# Teensy_CARD_V2.net
KiCad netlist of a schematic drawn in EAGLE
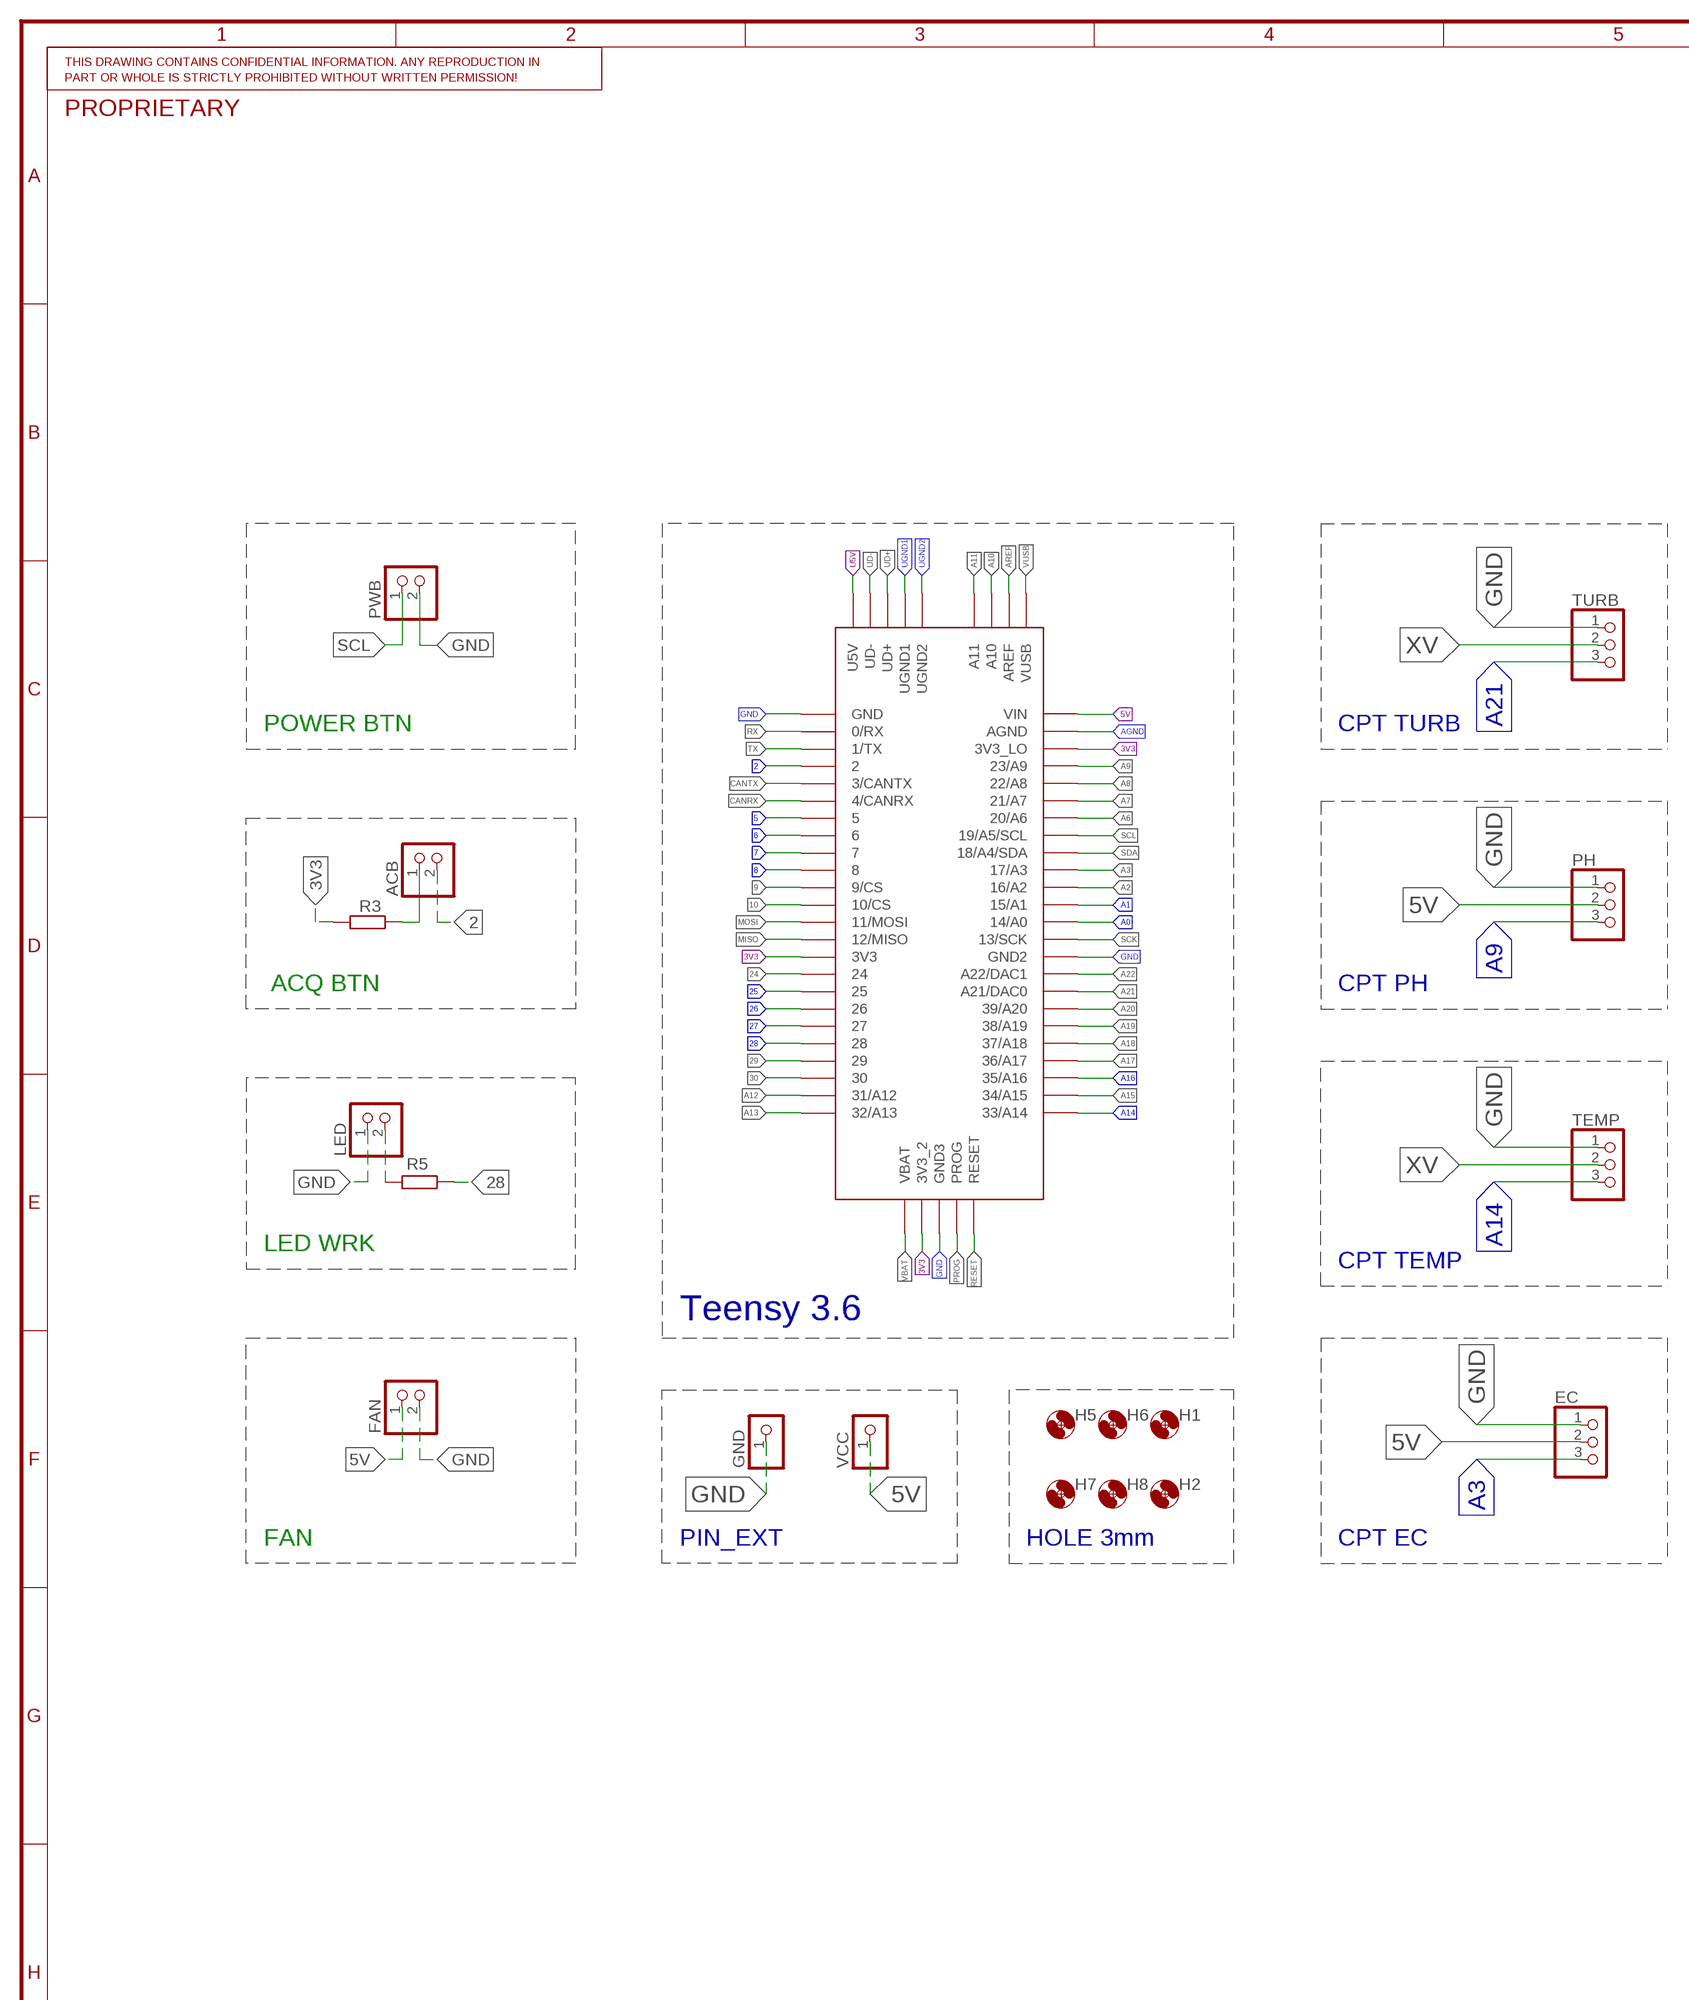
[diagram p0: schematic, sheet 1, part 1 of 2]
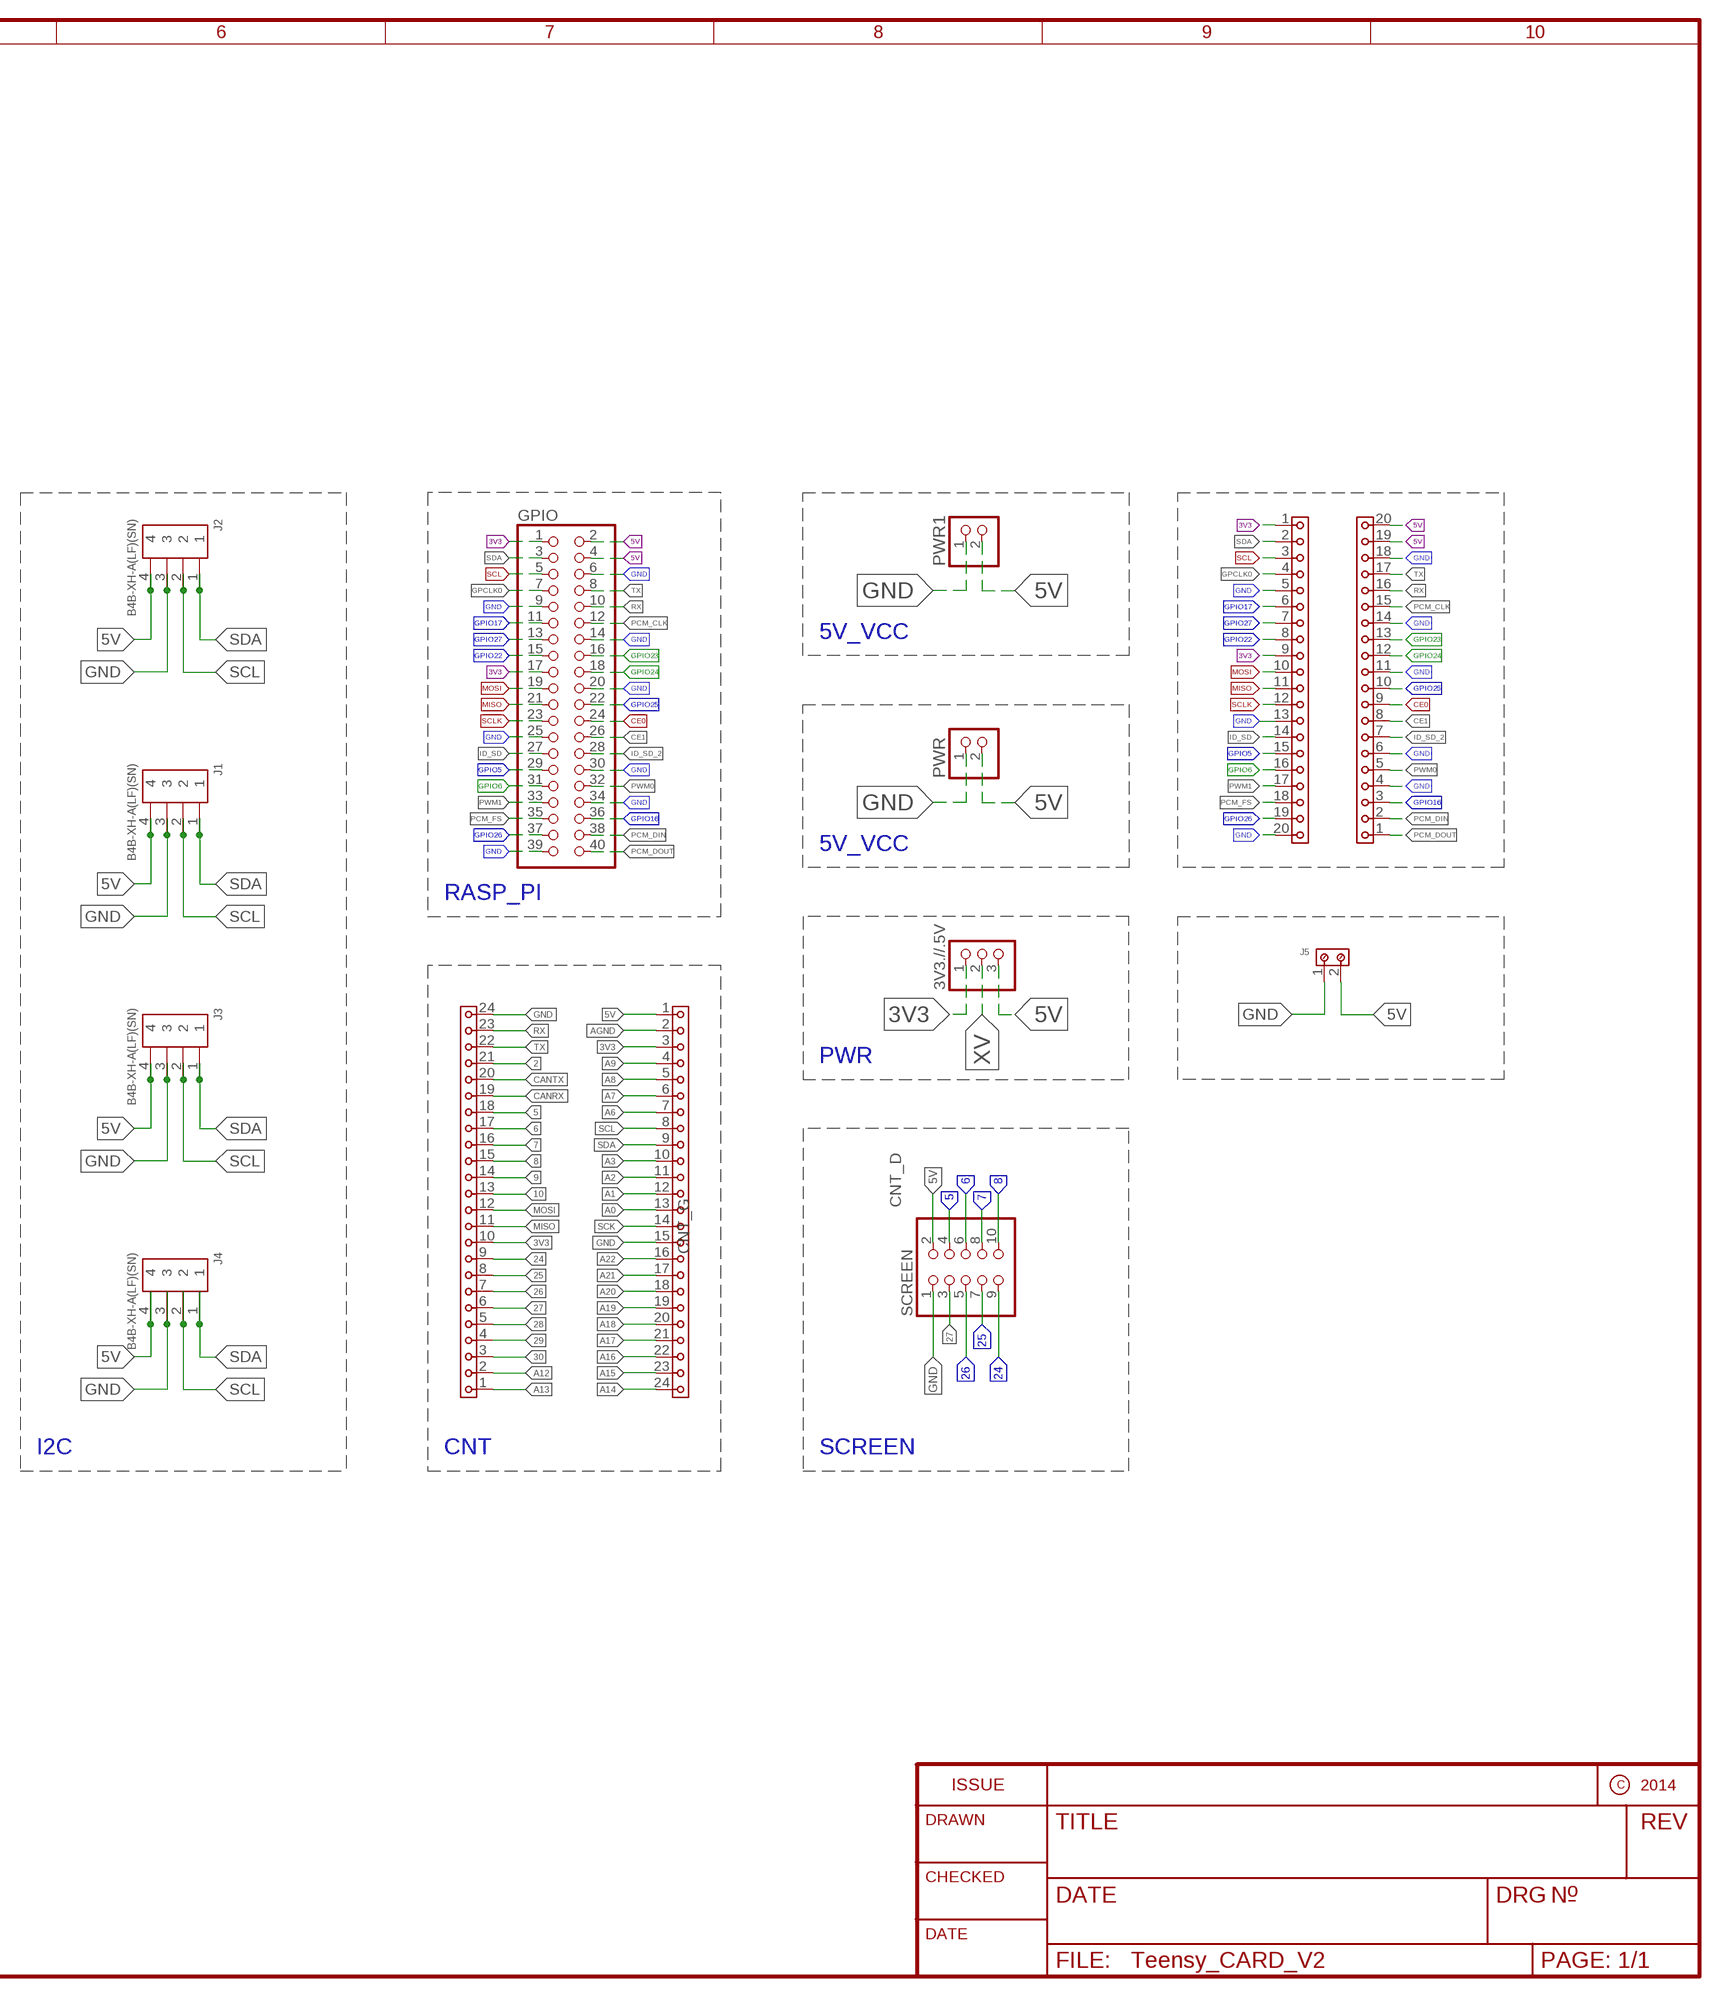
[diagram p1: schematic, sheet 1, part 2 of 2]

(export (version "E")
  (design (tool "Eeschema 10.0.6"))
  (components
    (comp (ref "3V3.//.5V")
      (value "PINHD-1X3")
      (footprint "eagle-import:1X03")
      (libsource (lib "eagle-import") (part "PINHD-1X3"))
    )
    (comp (ref "ACB")
      (value "PINHD-1X2")
      (footprint "eagle-import:1X02")
      (libsource (lib "eagle-import") (part "pinhead_325_PINHD-1X2"))
    )
    (comp (ref "CNT_D")
      (value "6130XX11821_61302411821")
      (footprint "eagle-import:61302411821")
      (libsource (lib "eagle-import") (part "6130XX11821_61302411821"))
    )
    (comp (ref "CNT_G")
      (value "6130XX11821_61302411821")
      (footprint "eagle-import:61302411821")
      (libsource (lib "eagle-import") (part "6130XX11821_61302411821"))
    )
    (comp (ref "EC")
      (value "PINHD-1X3")
      (footprint "eagle-import:1X03")
      (libsource (lib "eagle-import") (part "PINHD-1X3"))
    )
    (comp (ref "FAN")
      (value "PINHD-1X2")
      (footprint "eagle-import:1X02")
      (libsource (lib "eagle-import") (part "pinhead_325_PINHD-1X2"))
    )
    (comp (ref "GND")
      (value "PINHD-1X1")
      (footprint "eagle-import:1X01")
      (libsource (lib "eagle-import") (part "PINHD-1X1"))
    )
    (comp (ref "GPIO")
      (value "PINHD-2X20")
      (footprint "eagle-import:2X20")
      (libsource (lib "eagle-import") (part "PINHD-2X20"))
    )
    (comp (ref "H1")
      (value "MOUNT-HOLE3.0")
      (footprint "eagle-import:3,0")
      (libsource (lib "eagle-import") (part "MOUNT-HOLE3.0"))
    )
    (comp (ref "H2")
      (value "MOUNT-HOLE3.0")
      (footprint "eagle-import:3,0")
      (libsource (lib "eagle-import") (part "MOUNT-HOLE3.0"))
    )
    (comp (ref "H5")
      (value "MOUNT-HOLE3.0")
      (footprint "eagle-import:3,0")
      (libsource (lib "eagle-import") (part "MOUNT-HOLE3.0"))
    )
    (comp (ref "H6")
      (value "MOUNT-HOLE3.0")
      (footprint "eagle-import:3,0")
      (libsource (lib "eagle-import") (part "MOUNT-HOLE3.0"))
    )
    (comp (ref "H7")
      (value "MOUNT-HOLE3.0")
      (footprint "eagle-import:3,0")
      (libsource (lib "eagle-import") (part "MOUNT-HOLE3.0"))
    )
    (comp (ref "H8")
      (value "MOUNT-HOLE3.0")
      (footprint "eagle-import:3,0")
      (libsource (lib "eagle-import") (part "MOUNT-HOLE3.0"))
    )
    (comp (ref "J1")
      (value "B4B-XH-A(LF)(SN)")
      (footprint "eagle-import:B4B-XH-A(LF)(SN)")
      (fields
        (field (name "DIGIKEY_PARTNO") "455-2249-ND")
        (field (name "MANUFACTURER") "JST Sales America Inc.")
        (field (name "CREATED_BY") "PCBLayout.com")
      )
      (libsource (lib "eagle-import") (part "B4B-XH-A(LF)(SN)"))
    )
    (comp (ref "J2")
      (value "B4B-XH-A(LF)(SN)")
      (footprint "eagle-import:B4B-XH-A(LF)(SN)")
      (fields
        (field (name "DIGIKEY_PARTNO") "455-2249-ND")
        (field (name "MANUFACTURER") "JST Sales America Inc.")
        (field (name "CREATED_BY") "PCBLayout.com")
      )
      (libsource (lib "eagle-import") (part "B4B-XH-A(LF)(SN)"))
    )
    (comp (ref "J3")
      (value "B4B-XH-A(LF)(SN)")
      (footprint "eagle-import:B4B-XH-A(LF)(SN)")
      (fields
        (field (name "DIGIKEY_PARTNO") "455-2249-ND")
        (field (name "MANUFACTURER") "JST Sales America Inc.")
        (field (name "CREATED_BY") "PCBLayout.com")
      )
      (libsource (lib "eagle-import") (part "B4B-XH-A(LF)(SN)"))
    )
    (comp (ref "J4")
      (value "B4B-XH-A(LF)(SN)")
      (footprint "eagle-import:B4B-XH-A(LF)(SN)")
      (fields
        (field (name "DIGIKEY_PARTNO") "455-2249-ND")
        (field (name "MANUFACTURER") "JST Sales America Inc.")
        (field (name "CREATED_BY") "PCBLayout.com")
      )
      (libsource (lib "eagle-import") (part "B4B-XH-A(LF)(SN)"))
    )
    (comp (ref "J5")
      (value "691213510002")
      (footprint "eagle-import:691213510002")
      (libsource (lib "eagle-import") (part "691213510002"))
    )
    (comp (ref "JP1")
      (value "6130XX11821_61302011821")
      (footprint "eagle-import:61302011821")
      (libsource (lib "eagle-import") (part "6130XX11821_61302011821"))
    )
    (comp (ref "JP2")
      (value "6130XX11821_61302011821")
      (footprint "eagle-import:61302011821")
      (libsource (lib "eagle-import") (part "6130XX11821_61302011821"))
    )
    (comp (ref "LED")
      (value "PINHD-1X2")
      (footprint "eagle-import:1X02")
      (libsource (lib "eagle-import") (part "pinhead_325_PINHD-1X2"))
    )
    (comp (ref "PH")
      (value "PINHD-1X3")
      (footprint "eagle-import:1X03")
      (libsource (lib "eagle-import") (part "PINHD-1X3"))
    )
    (comp (ref "PWB")
      (value "PINHD-1X2")
      (footprint "eagle-import:1X02")
      (libsource (lib "eagle-import") (part "pinhead_325_PINHD-1X2"))
    )
    (comp (ref "PWR")
      (value "PINHD-1X2")
      (footprint "eagle-import:1X02")
      (libsource (lib "eagle-import") (part "PINHD-1X2"))
    )
    (comp (ref "PWR1")
      (value "PINHD-1X2")
      (footprint "eagle-import:1X02")
      (libsource (lib "eagle-import") (part "PINHD-1X2"))
    )
    (comp (ref "R3")
      (value "R-EU_0207/10")
      (footprint "eagle-import:0207_10")
      (libsource (lib "eagle-import") (part "R-EU_0207/10"))
    )
    (comp (ref "R5")
      (value "R-EU_0207/10")
      (footprint "eagle-import:0207_10")
      (libsource (lib "eagle-import") (part "R-EU_0207/10"))
    )
    (comp (ref "SCREEN")
      (value "PINHD-2X5")
      (footprint "eagle-import:2X05")
      (libsource (lib "eagle-import") (part "PINHD-2X5"))
    )
    (comp (ref "TEMP")
      (value "PINHD-1X3")
      (footprint "eagle-import:1X03")
      (libsource (lib "eagle-import") (part "PINHD-1X3"))
    )
    (comp (ref "TURB")
      (value "PINHD-1X3")
      (footprint "eagle-import:1X03")
      (libsource (lib "eagle-import") (part "PINHD-1X3"))
    )
    (comp (ref "U$1")
      (value "TEENSY_3.5/3.6")
      (footprint "eagle-import:TEENSY_3.5_3.6")
      (libsource (lib "eagle-import") (part "TEENSY_3.5/3.6"))
    )
    (comp (ref "VCC")
      (value "PINHD-1X1")
      (footprint "eagle-import:1X01")
      (libsource (lib "eagle-import") (part "PINHD-1X1"))
    )
  )
  (nets
    (net (code "1") (name "2") (class "Default")
      (node (ref "ACB") (pin "2") (pinfunction "2_2") (pintype "passive"))
      (node (ref "CNT_G") (pin "21") (pinfunction "21_21") (pintype "passive"))
      (node (ref "U$1") (pin "2") (pinfunction "2_2") (pintype "bidirectional"))
    )
    (net (code "2") (name "3V3") (class "Default")
      (node (ref "3V3.//.5V") (pin "1") (pinfunction "1_1") (pintype "passive"))
      (node (ref "CNT_D") (pin "3") (pinfunction "3_3") (pintype "passive"))
      (node (ref "CNT_G") (pin "10") (pinfunction "10_10") (pintype "passive"))
      (node (ref "GPIO") (pin "1") (pinfunction "1_1") (pintype "passive"))
      (node (ref "GPIO") (pin "17") (pinfunction "17_17") (pintype "passive"))
      (node (ref "JP1") (pin "1") (pinfunction "1_1") (pintype "passive"))
      (node (ref "JP1") (pin "9") (pinfunction "9_9") (pintype "passive"))
      (node (ref "R3") (pin "1") (pinfunction "1_1") (pintype "passive"))
      (node (ref "U$1") (pin "3V3") (pinfunction "3V3_3V3") (pintype "bidirectional"))
      (node (ref "U$1") (pin "3V3_2") (pinfunction "3V3_2_3V3_2") (pintype "bidirectional"))
      (node (ref "U$1") (pin "3V3_LO") (pinfunction "3V3_LO_3V3_LO") (pintype "bidirectional"))
    )
    (net (code "3") (name "5") (class "Default")
      (node (ref "CNT_G") (pin "18") (pinfunction "18_18") (pintype "passive"))
      (node (ref "SCREEN") (pin "4") (pinfunction "4_4") (pintype "passive"))
      (node (ref "U$1") (pin "5") (pinfunction "5_5") (pintype "bidirectional"))
    )
    (net (code "4") (name "5V") (class "Default")
      (node (ref "3V3.//.5V") (pin "3") (pinfunction "3_3") (pintype "passive"))
      (node (ref "CNT_D") (pin "1") (pinfunction "1_1") (pintype "passive"))
      (node (ref "EC") (pin "2") (pinfunction "2_2") (pintype "passive"))
      (node (ref "FAN") (pin "1") (pinfunction "1_1") (pintype "passive"))
      (node (ref "GPIO") (pin "2") (pinfunction "2_2") (pintype "passive"))
      (node (ref "GPIO") (pin "4") (pinfunction "4_4") (pintype "passive"))
      (node (ref "J1") (pin "4") (pinfunction "4_4") (pintype "passive"))
      (node (ref "J2") (pin "4") (pinfunction "4_4") (pintype "passive"))
      (node (ref "J3") (pin "4") (pinfunction "4_4") (pintype "passive"))
      (node (ref "J4") (pin "4") (pinfunction "4_4") (pintype "passive"))
      (node (ref "J5") (pin "2") (pinfunction "2_2") (pintype "passive"))
      (node (ref "JP2") (pin "19") (pinfunction "19_19") (pintype "passive"))
      (node (ref "JP2") (pin "20") (pinfunction "20_20") (pintype "passive"))
      (node (ref "PH") (pin "2") (pinfunction "2_2") (pintype "passive"))
      (node (ref "PWR") (pin "2") (pinfunction "2_2") (pintype "passive"))
      (node (ref "PWR1") (pin "2") (pinfunction "2_2") (pintype "passive"))
      (node (ref "SCREEN") (pin "2") (pinfunction "2_2") (pintype "passive"))
      (node (ref "U$1") (pin "VIN") (pinfunction "VIN_VIN") (pintype "bidirectional"))
      (node (ref "VCC") (pin "1") (pinfunction "1_1") (pintype "passive"))
    )
    (net (code "5") (name "6") (class "Default")
      (node (ref "CNT_G") (pin "17") (pinfunction "17_17") (pintype "passive"))
      (node (ref "SCREEN") (pin "6") (pinfunction "6_6") (pintype "passive"))
      (node (ref "U$1") (pin "6") (pinfunction "6_6") (pintype "bidirectional"))
    )
    (net (code "6") (name "7") (class "Default")
      (node (ref "CNT_G") (pin "16") (pinfunction "16_16") (pintype "passive"))
      (node (ref "SCREEN") (pin "8") (pinfunction "8_8") (pintype "passive"))
      (node (ref "U$1") (pin "7") (pinfunction "7_7") (pintype "bidirectional"))
    )
    (net (code "7") (name "8") (class "Default")
      (node (ref "CNT_G") (pin "15") (pinfunction "15_15") (pintype "passive"))
      (node (ref "SCREEN") (pin "10") (pinfunction "10_10") (pintype "passive"))
      (node (ref "U$1") (pin "8") (pinfunction "8_8") (pintype "bidirectional"))
    )
    (net (code "8") (name "9") (class "Default")
      (node (ref "CNT_G") (pin "14") (pinfunction "14_14") (pintype "passive"))
      (node (ref "U$1") (pin "9/CS") (pinfunction "9/CS_9/CS") (pintype "bidirectional"))
    )
    (net (code "9") (name "10") (class "Default")
      (node (ref "CNT_G") (pin "13") (pinfunction "13_13") (pintype "passive"))
      (node (ref "U$1") (pin "10/CS") (pinfunction "10/CS_10/CS") (pintype "bidirectional"))
    )
    (net (code "10") (name "24") (class "Default")
      (node (ref "CNT_G") (pin "9") (pinfunction "9_9") (pintype "passive"))
      (node (ref "SCREEN") (pin "9") (pinfunction "9_9") (pintype "passive"))
      (node (ref "U$1") (pin "24") (pinfunction "24_24") (pintype "bidirectional"))
    )
    (net (code "11") (name "25") (class "Default")
      (node (ref "CNT_G") (pin "8") (pinfunction "8_8") (pintype "passive"))
      (node (ref "SCREEN") (pin "7") (pinfunction "7_7") (pintype "passive"))
      (node (ref "U$1") (pin "25") (pinfunction "25_25") (pintype "bidirectional"))
    )
    (net (code "12") (name "26") (class "Default")
      (node (ref "CNT_G") (pin "7") (pinfunction "7_7") (pintype "passive"))
      (node (ref "SCREEN") (pin "5") (pinfunction "5_5") (pintype "passive"))
      (node (ref "U$1") (pin "26") (pinfunction "26_26") (pintype "bidirectional"))
    )
    (net (code "13") (name "27") (class "Default")
      (node (ref "CNT_G") (pin "6") (pinfunction "6_6") (pintype "passive"))
      (node (ref "SCREEN") (pin "3") (pinfunction "3_3") (pintype "passive"))
      (node (ref "U$1") (pin "27") (pinfunction "27_27") (pintype "bidirectional"))
    )
    (net (code "14") (name "28") (class "Default")
      (node (ref "CNT_G") (pin "5") (pinfunction "5_5") (pintype "passive"))
      (node (ref "R5") (pin "1") (pinfunction "1_1") (pintype "passive"))
      (node (ref "U$1") (pin "28") (pinfunction "28_28") (pintype "bidirectional"))
    )
    (net (code "15") (name "29") (class "Default")
      (node (ref "CNT_G") (pin "4") (pinfunction "4_4") (pintype "passive"))
      (node (ref "U$1") (pin "29") (pinfunction "29_29") (pintype "bidirectional"))
    )
    (net (code "16") (name "30") (class "Default")
      (node (ref "CNT_G") (pin "3") (pinfunction "3_3") (pintype "passive"))
      (node (ref "U$1") (pin "30") (pinfunction "30_30") (pintype "bidirectional"))
    )
    (net (code "17") (name "A0") (class "Default")
      (node (ref "CNT_D") (pin "13") (pinfunction "13_13") (pintype "passive"))
      (node (ref "U$1") (pin "14/A0") (pinfunction "14/A0_14/A0") (pintype "bidirectional"))
    )
    (net (code "18") (name "A1") (class "Default")
      (node (ref "CNT_D") (pin "12") (pinfunction "12_12") (pintype "passive"))
      (node (ref "U$1") (pin "15/A1") (pinfunction "15/A1_15/A1") (pintype "bidirectional"))
    )
    (net (code "19") (name "A2") (class "Default")
      (node (ref "CNT_D") (pin "11") (pinfunction "11_11") (pintype "passive"))
      (node (ref "U$1") (pin "16/A2") (pinfunction "16/A2_16/A2") (pintype "bidirectional"))
    )
    (net (code "20") (name "A3") (class "Default")
      (node (ref "CNT_D") (pin "10") (pinfunction "10_10") (pintype "passive"))
      (node (ref "EC") (pin "3") (pinfunction "3_3") (pintype "passive"))
      (node (ref "U$1") (pin "17/A3") (pinfunction "17/A3_17/A3") (pintype "bidirectional"))
    )
    (net (code "21") (name "A6") (class "Default")
      (node (ref "CNT_D") (pin "7") (pinfunction "7_7") (pintype "passive"))
      (node (ref "U$1") (pin "20/A6") (pinfunction "20/A6_20/A6") (pintype "bidirectional"))
    )
    (net (code "22") (name "A7") (class "Default")
      (node (ref "CNT_D") (pin "6") (pinfunction "6_6") (pintype "passive"))
      (node (ref "U$1") (pin "21/A7") (pinfunction "21/A7_21/A7") (pintype "bidirectional"))
    )
    (net (code "23") (name "A8") (class "Default")
      (node (ref "CNT_D") (pin "5") (pinfunction "5_5") (pintype "passive"))
      (node (ref "U$1") (pin "22/A8") (pinfunction "22/A8_22/A8") (pintype "bidirectional"))
    )
    (net (code "24") (name "A9") (class "Default")
      (node (ref "CNT_D") (pin "4") (pinfunction "4_4") (pintype "passive"))
      (node (ref "PH") (pin "3") (pinfunction "3_3") (pintype "passive"))
      (node (ref "U$1") (pin "23/A9") (pinfunction "23/A9_23/A9") (pintype "bidirectional"))
    )
    (net (code "25") (name "A10") (class "Default")
      (node (ref "U$1") (pin "A10") (pinfunction "A10_A10") (pintype "bidirectional"))
    )
    (net (code "26") (name "A11") (class "Default")
      (node (ref "U$1") (pin "A11") (pinfunction "A11_A11") (pintype "bidirectional"))
    )
    (net (code "27") (name "A12") (class "Default")
      (node (ref "CNT_G") (pin "2") (pinfunction "2_2") (pintype "passive"))
      (node (ref "U$1") (pin "31/A12") (pinfunction "31/A12_31/A12") (pintype "bidirectional"))
    )
    (net (code "28") (name "A13") (class "Default")
      (node (ref "CNT_G") (pin "1") (pinfunction "1_1") (pintype "passive"))
      (node (ref "U$1") (pin "32/A13") (pinfunction "32/A13_32/A13") (pintype "bidirectional"))
    )
    (net (code "29") (name "A14") (class "Default")
      (node (ref "CNT_D") (pin "24") (pinfunction "24_24") (pintype "passive"))
      (node (ref "TEMP") (pin "3") (pinfunction "3_3") (pintype "passive"))
      (node (ref "U$1") (pin "33/A14") (pinfunction "33/A14_33/A14") (pintype "bidirectional"))
    )
    (net (code "30") (name "A15") (class "Default")
      (node (ref "CNT_D") (pin "23") (pinfunction "23_23") (pintype "passive"))
      (node (ref "U$1") (pin "34/A15") (pinfunction "34/A15_34/A15") (pintype "bidirectional"))
    )
    (net (code "31") (name "A16") (class "Default")
      (node (ref "CNT_D") (pin "22") (pinfunction "22_22") (pintype "passive"))
      (node (ref "U$1") (pin "35/A16") (pinfunction "35/A16_35/A16") (pintype "bidirectional"))
    )
    (net (code "32") (name "A17") (class "Default")
      (node (ref "CNT_D") (pin "21") (pinfunction "21_21") (pintype "passive"))
      (node (ref "U$1") (pin "36/A17") (pinfunction "36/A17_36/A17") (pintype "bidirectional"))
    )
    (net (code "33") (name "A18") (class "Default")
      (node (ref "CNT_D") (pin "20") (pinfunction "20_20") (pintype "passive"))
      (node (ref "U$1") (pin "37/A18") (pinfunction "37/A18_37/A18") (pintype "bidirectional"))
    )
    (net (code "34") (name "A19") (class "Default")
      (node (ref "CNT_D") (pin "19") (pinfunction "19_19") (pintype "passive"))
      (node (ref "U$1") (pin "38/A19") (pinfunction "38/A19_38/A19") (pintype "bidirectional"))
    )
    (net (code "35") (name "A20") (class "Default")
      (node (ref "CNT_D") (pin "18") (pinfunction "18_18") (pintype "passive"))
      (node (ref "U$1") (pin "39/A20") (pinfunction "39/A20_39/A20") (pintype "bidirectional"))
    )
    (net (code "36") (name "A21") (class "Default")
      (node (ref "CNT_D") (pin "17") (pinfunction "17_17") (pintype "passive"))
      (node (ref "TURB") (pin "3") (pinfunction "3_3") (pintype "passive"))
      (node (ref "U$1") (pin "21/DAC0") (pinfunction "A21/DAC0_21/DAC0") (pintype "bidirectional"))
    )
    (net (code "37") (name "A22") (class "Default")
      (node (ref "CNT_D") (pin "16") (pinfunction "16_16") (pintype "passive"))
      (node (ref "U$1") (pin "A22/DAC1") (pinfunction "A22/DAC1_A22/DAC1") (pintype "bidirectional"))
    )
    (net (code "38") (name "AGND") (class "Default")
      (node (ref "CNT_D") (pin "2") (pinfunction "2_2") (pintype "passive"))
      (node (ref "U$1") (pin "AGND") (pinfunction "AGND_AGND") (pintype "bidirectional"))
    )
    (net (code "39") (name "AREF") (class "Default")
      (node (ref "U$1") (pin "AREF") (pinfunction "AREF_AREF") (pintype "bidirectional"))
    )
    (net (code "40") (name "CANRX") (class "Default")
      (node (ref "CNT_G") (pin "19") (pinfunction "19_19") (pintype "passive"))
      (node (ref "U$1") (pin "4/CANRX") (pinfunction "4/CANRX_4/CANRX") (pintype "bidirectional"))
    )
    (net (code "41") (name "CANTX") (class "Default")
      (node (ref "CNT_G") (pin "20") (pinfunction "20_20") (pintype "passive"))
      (node (ref "U$1") (pin "3/CANTX") (pinfunction "3/CANTX_3/CANTX") (pintype "bidirectional"))
    )
    (net (code "42") (name "CE0") (class "Default")
      (node (ref "GPIO") (pin "24") (pinfunction "24_24") (pintype "passive"))
      (node (ref "JP2") (pin "9") (pinfunction "9_9") (pintype "passive"))
    )
    (net (code "43") (name "CE1") (class "Default")
      (node (ref "GPIO") (pin "26") (pinfunction "26_26") (pintype "passive"))
      (node (ref "JP2") (pin "8") (pinfunction "8_8") (pintype "passive"))
    )
    (net (code "44") (name "GND") (class "Default")
      (node (ref "CNT_D") (pin "15") (pinfunction "15_15") (pintype "passive"))
      (node (ref "CNT_G") (pin "24") (pinfunction "24_24") (pintype "passive"))
      (node (ref "EC") (pin "1") (pinfunction "1_1") (pintype "passive"))
      (node (ref "FAN") (pin "2") (pinfunction "2_2") (pintype "passive"))
      (node (ref "GND") (pin "1") (pinfunction "1_1") (pintype "passive"))
      (node (ref "GPIO") (pin "14") (pinfunction "14_14") (pintype "passive"))
      (node (ref "GPIO") (pin "20") (pinfunction "20_20") (pintype "passive"))
      (node (ref "GPIO") (pin "25") (pinfunction "25_25") (pintype "passive"))
      (node (ref "GPIO") (pin "30") (pinfunction "30_30") (pintype "passive"))
      (node (ref "GPIO") (pin "34") (pinfunction "34_34") (pintype "passive"))
      (node (ref "GPIO") (pin "39") (pinfunction "39_39") (pintype "passive"))
      (node (ref "GPIO") (pin "6") (pinfunction "6_6") (pintype "passive"))
      (node (ref "GPIO") (pin "9") (pinfunction "9_9") (pintype "passive"))
      (node (ref "J1") (pin "3") (pinfunction "3_3") (pintype "passive"))
      (node (ref "J2") (pin "3") (pinfunction "3_3") (pintype "passive"))
      (node (ref "J3") (pin "3") (pinfunction "3_3") (pintype "passive"))
      (node (ref "J4") (pin "3") (pinfunction "3_3") (pintype "passive"))
      (node (ref "J5") (pin "1") (pinfunction "1_1") (pintype "passive"))
      (node (ref "JP1") (pin "13") (pinfunction "13_13") (pintype "passive"))
      (node (ref "JP1") (pin "20") (pinfunction "20_20") (pintype "passive"))
      (node (ref "JP1") (pin "5") (pinfunction "5_5") (pintype "passive"))
      (node (ref "JP2") (pin "11") (pinfunction "11_11") (pintype "passive"))
      (node (ref "JP2") (pin "14") (pinfunction "14_14") (pintype "passive"))
      (node (ref "JP2") (pin "18") (pinfunction "18_18") (pintype "passive"))
      (node (ref "JP2") (pin "4") (pinfunction "4_4") (pintype "passive"))
      (node (ref "JP2") (pin "6") (pinfunction "6_6") (pintype "passive"))
      (node (ref "LED") (pin "1") (pinfunction "1_1") (pintype "passive"))
      (node (ref "PH") (pin "1") (pinfunction "1_1") (pintype "passive"))
      (node (ref "PWB") (pin "2") (pinfunction "2_2") (pintype "passive"))
      (node (ref "PWR") (pin "1") (pinfunction "1_1") (pintype "passive"))
      (node (ref "PWR1") (pin "1") (pinfunction "1_1") (pintype "passive"))
      (node (ref "SCREEN") (pin "1") (pinfunction "1_1") (pintype "passive"))
      (node (ref "TEMP") (pin "1") (pinfunction "1_1") (pintype "passive"))
      (node (ref "TURB") (pin "1") (pinfunction "1_1") (pintype "passive"))
      (node (ref "U$1") (pin "GND") (pinfunction "GND_GND") (pintype "bidirectional"))
      (node (ref "U$1") (pin "GND2") (pinfunction "GND2_GND2") (pintype "bidirectional"))
      (node (ref "U$1") (pin "GND3") (pinfunction "GND3_GND3") (pintype "bidirectional"))
    )
    (net (code "45") (name "GPCLK0") (class "Default")
      (node (ref "GPIO") (pin "7") (pinfunction "7_7") (pintype "passive"))
      (node (ref "JP1") (pin "4") (pinfunction "4_4") (pintype "passive"))
    )
    (net (code "46") (name "GPIO5") (class "Default")
      (node (ref "GPIO") (pin "29") (pinfunction "29_29") (pintype "passive"))
      (node (ref "JP1") (pin "15") (pinfunction "15_15") (pintype "passive"))
    )
    (net (code "47") (name "GPIO6") (class "Default")
      (node (ref "GPIO") (pin "31") (pinfunction "31_31") (pintype "passive"))
      (node (ref "JP1") (pin "16") (pinfunction "16_16") (pintype "passive"))
    )
    (net (code "48") (name "GPIO16") (class "Default")
      (node (ref "GPIO") (pin "36") (pinfunction "36_36") (pintype "passive"))
      (node (ref "JP2") (pin "3") (pinfunction "3_3") (pintype "passive"))
    )
    (net (code "49") (name "GPIO17") (class "Default")
      (node (ref "GPIO") (pin "11") (pinfunction "11_11") (pintype "passive"))
      (node (ref "JP1") (pin "6") (pinfunction "6_6") (pintype "passive"))
    )
    (net (code "50") (name "GPIO22") (class "Default")
      (node (ref "GPIO") (pin "15") (pinfunction "15_15") (pintype "passive"))
      (node (ref "JP1") (pin "8") (pinfunction "8_8") (pintype "passive"))
    )
    (net (code "51") (name "GPIO23") (class "Default")
      (node (ref "GPIO") (pin "16") (pinfunction "16_16") (pintype "passive"))
      (node (ref "JP2") (pin "13") (pinfunction "13_13") (pintype "passive"))
    )
    (net (code "52") (name "GPIO24") (class "Default")
      (node (ref "GPIO") (pin "18") (pinfunction "18_18") (pintype "passive"))
      (node (ref "JP2") (pin "12") (pinfunction "12_12") (pintype "passive"))
    )
    (net (code "53") (name "GPIO25") (class "Default")
      (node (ref "GPIO") (pin "22") (pinfunction "22_22") (pintype "passive"))
      (node (ref "JP2") (pin "10") (pinfunction "10_10") (pintype "passive"))
    )
    (net (code "54") (name "GPIO26") (class "Default")
      (node (ref "GPIO") (pin "37") (pinfunction "37_37") (pintype "passive"))
      (node (ref "JP1") (pin "19") (pinfunction "19_19") (pintype "passive"))
    )
    (net (code "55") (name "GPIO27") (class "Default")
      (node (ref "GPIO") (pin "13") (pinfunction "13_13") (pintype "passive"))
      (node (ref "JP1") (pin "7") (pinfunction "7_7") (pintype "passive"))
    )
    (net (code "56") (name "ID_SD") (class "Default")
      (node (ref "GPIO") (pin "27") (pinfunction "27_27") (pintype "passive"))
      (node (ref "JP1") (pin "14") (pinfunction "14_14") (pintype "passive"))
    )
    (net (code "57") (name "ID_SD_2") (class "Default")
      (node (ref "GPIO") (pin "28") (pinfunction "28_28") (pintype "passive"))
      (node (ref "JP2") (pin "7") (pinfunction "7_7") (pintype "passive"))
    )
    (net (code "58") (name "MISO") (class "Default")
      (node (ref "CNT_G") (pin "11") (pinfunction "11_11") (pintype "passive"))
      (node (ref "GPIO") (pin "21") (pinfunction "21_21") (pintype "passive"))
      (node (ref "JP1") (pin "11") (pinfunction "11_11") (pintype "passive"))
      (node (ref "U$1") (pin "12/MISO") (pinfunction "12/MISO_12/MISO") (pintype "bidirectional"))
    )
    (net (code "59") (name "MOSI") (class "Default")
      (node (ref "CNT_G") (pin "12") (pinfunction "12_12") (pintype "passive"))
      (node (ref "GPIO") (pin "19") (pinfunction "19_19") (pintype "passive"))
      (node (ref "JP1") (pin "10") (pinfunction "10_10") (pintype "passive"))
      (node (ref "U$1") (pin "11/MOSI") (pinfunction "11/MOSI_11/MOSI") (pintype "bidirectional"))
    )
    (net (code "60") (name "Net-(ACB-Pad1)") (class "Default")
      (node (ref "ACB") (pin "1") (pinfunction "1_1") (pintype "passive"))
      (node (ref "R3") (pin "2") (pinfunction "2_2") (pintype "passive"))
    )
    (net (code "61") (name "Net-(LED-Pad2)") (class "Default")
      (node (ref "LED") (pin "2") (pinfunction "2_2") (pintype "passive"))
      (node (ref "R5") (pin "2") (pinfunction "2_2") (pintype "passive"))
    )
    (net (code "62") (name "PCM_CLK") (class "Default")
      (node (ref "GPIO") (pin "12") (pinfunction "12_12") (pintype "passive"))
      (node (ref "JP2") (pin "15") (pinfunction "15_15") (pintype "passive"))
    )
    (net (code "63") (name "PCM_DIN") (class "Default")
      (node (ref "GPIO") (pin "38") (pinfunction "38_38") (pintype "passive"))
      (node (ref "JP2") (pin "2") (pinfunction "2_2") (pintype "passive"))
    )
    (net (code "64") (name "PCM_DOUT") (class "Default")
      (node (ref "GPIO") (pin "40") (pinfunction "40_40") (pintype "passive"))
      (node (ref "JP2") (pin "1") (pinfunction "1_1") (pintype "passive"))
    )
    (net (code "65") (name "PCM_FS") (class "Default")
      (node (ref "GPIO") (pin "35") (pinfunction "35_35") (pintype "passive"))
      (node (ref "JP1") (pin "18") (pinfunction "18_18") (pintype "passive"))
    )
    (net (code "66") (name "PROG") (class "Default")
      (node (ref "U$1") (pin "PROG") (pinfunction "PROG_PROG") (pintype "bidirectional"))
    )
    (net (code "67") (name "PWM0") (class "Default")
      (node (ref "GPIO") (pin "32") (pinfunction "32_32") (pintype "passive"))
      (node (ref "JP2") (pin "5") (pinfunction "5_5") (pintype "passive"))
    )
    (net (code "68") (name "PWM1") (class "Default")
      (node (ref "GPIO") (pin "33") (pinfunction "33_33") (pintype "passive"))
      (node (ref "JP1") (pin "17") (pinfunction "17_17") (pintype "passive"))
    )
    (net (code "69") (name "RESET") (class "Default")
      (node (ref "U$1") (pin "RESET") (pinfunction "RESET_RESET") (pintype "bidirectional"))
    )
    (net (code "70") (name "RX") (class "Default")
      (node (ref "CNT_G") (pin "23") (pinfunction "23_23") (pintype "passive"))
      (node (ref "GPIO") (pin "10") (pinfunction "10_10") (pintype "passive"))
      (node (ref "JP2") (pin "16") (pinfunction "16_16") (pintype "passive"))
      (node (ref "U$1") (pin "0/RX") (pinfunction "0/RX_0/RX") (pintype "bidirectional"))
    )
    (net (code "71") (name "SCK") (class "Default")
      (node (ref "CNT_D") (pin "14") (pinfunction "14_14") (pintype "passive"))
      (node (ref "U$1") (pin "13/SCK") (pinfunction "13/SCK_13/SCK") (pintype "bidirectional"))
    )
    (net (code "72") (name "SCL") (class "Default")
      (node (ref "CNT_D") (pin "8") (pinfunction "8_8") (pintype "passive"))
      (node (ref "GPIO") (pin "5") (pinfunction "5_5") (pintype "passive"))
      (node (ref "J1") (pin "2") (pinfunction "2_2") (pintype "passive"))
      (node (ref "J2") (pin "2") (pinfunction "2_2") (pintype "passive"))
      (node (ref "J3") (pin "2") (pinfunction "2_2") (pintype "passive"))
      (node (ref "J4") (pin "2") (pinfunction "2_2") (pintype "passive"))
      (node (ref "JP1") (pin "3") (pinfunction "3_3") (pintype "passive"))
      (node (ref "PWB") (pin "1") (pinfunction "1_1") (pintype "passive"))
      (node (ref "U$1") (pin "19/A5/SCL") (pinfunction "19/A5/SCL_19/A5/SCL") (pintype "bidirectional"))
    )
    (net (code "73") (name "SCLK") (class "Default")
      (node (ref "GPIO") (pin "23") (pinfunction "23_23") (pintype "passive"))
      (node (ref "JP1") (pin "12") (pinfunction "12_12") (pintype "passive"))
    )
    (net (code "74") (name "SDA") (class "Default")
      (node (ref "CNT_D") (pin "9") (pinfunction "9_9") (pintype "passive"))
      (node (ref "GPIO") (pin "3") (pinfunction "3_3") (pintype "passive"))
      (node (ref "J1") (pin "1") (pinfunction "1_1") (pintype "passive"))
      (node (ref "J2") (pin "1") (pinfunction "1_1") (pintype "passive"))
      (node (ref "J3") (pin "1") (pinfunction "1_1") (pintype "passive"))
      (node (ref "J4") (pin "1") (pinfunction "1_1") (pintype "passive"))
      (node (ref "JP1") (pin "2") (pinfunction "2_2") (pintype "passive"))
      (node (ref "U$1") (pin "18/A4/SDA") (pinfunction "18/A4/SDA_18/A4/SDA") (pintype "bidirectional"))
    )
    (net (code "75") (name "TX") (class "Default")
      (node (ref "CNT_G") (pin "22") (pinfunction "22_22") (pintype "passive"))
      (node (ref "GPIO") (pin "8") (pinfunction "8_8") (pintype "passive"))
      (node (ref "JP2") (pin "17") (pinfunction "17_17") (pintype "passive"))
      (node (ref "U$1") (pin "1/TX") (pinfunction "1/TX_1/TX") (pintype "bidirectional"))
    )
    (net (code "76") (name "U5V") (class "Default")
      (node (ref "U$1") (pin "U5V") (pinfunction "U5V_U5V") (pintype "bidirectional"))
    )
    (net (code "77") (name "UD+") (class "Default")
      (node (ref "U$1") (pin "UD+") (pinfunction "UD+_UD+") (pintype "bidirectional"))
    )
    (net (code "78") (name "UD-") (class "Default")
      (node (ref "U$1") (pin "UD-") (pinfunction "UD-_UD-") (pintype "bidirectional"))
    )
    (net (code "79") (name "UGND1") (class "Default")
      (node (ref "U$1") (pin "UGND1") (pinfunction "UGND1_UGND1") (pintype "bidirectional"))
    )
    (net (code "80") (name "UGND2") (class "Default")
      (node (ref "U$1") (pin "UGND2") (pinfunction "UGND2_UGND2") (pintype "bidirectional"))
    )
    (net (code "81") (name "VBAT") (class "Default")
      (node (ref "U$1") (pin "VBAT") (pinfunction "VBAT_VBAT") (pintype "bidirectional"))
    )
    (net (code "82") (name "VUSB") (class "Default")
      (node (ref "U$1") (pin "VUSB") (pinfunction "VUSB_VUSB") (pintype "bidirectional"))
    )
    (net (code "83") (name "XV") (class "Default")
      (node (ref "3V3.//.5V") (pin "2") (pinfunction "2_2") (pintype "passive"))
      (node (ref "TEMP") (pin "2") (pinfunction "2_2") (pintype "passive"))
      (node (ref "TURB") (pin "2") (pinfunction "2_2") (pintype "passive"))
    )
  )
)
